# 05_MCU_C.net
KiCad netlist of a schematic drawn in Altium Designer
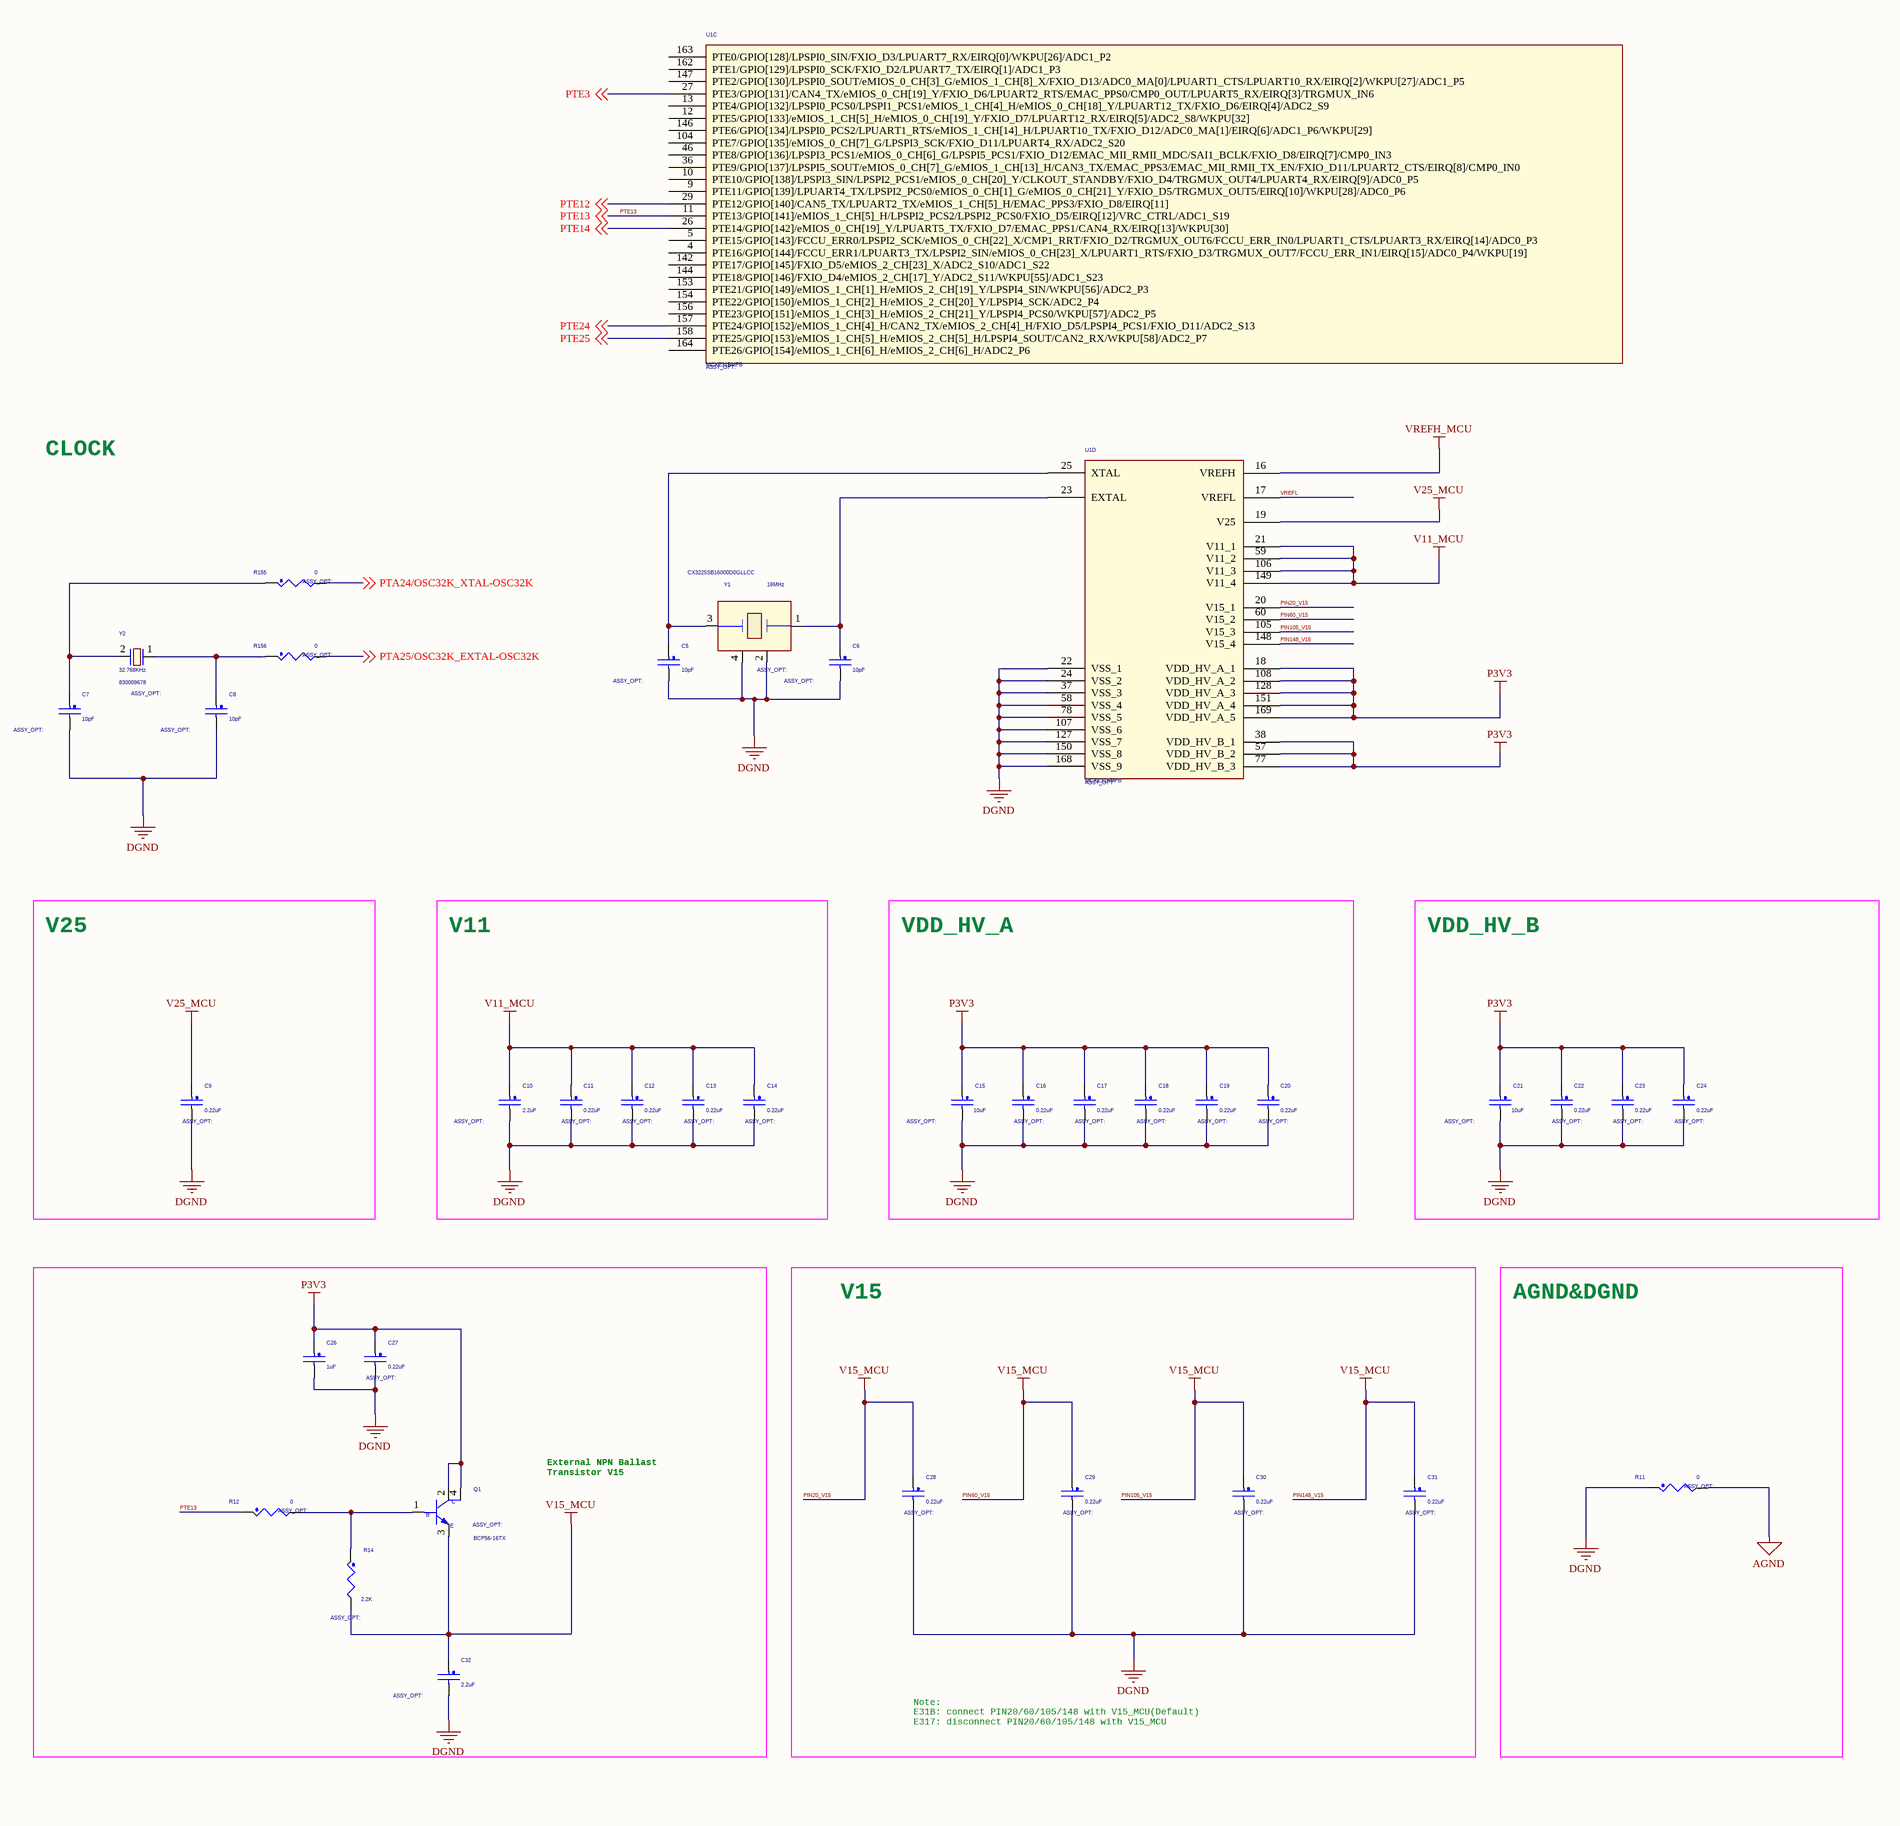
[diagram p0: 05 MCU_C.SchDoc, left]
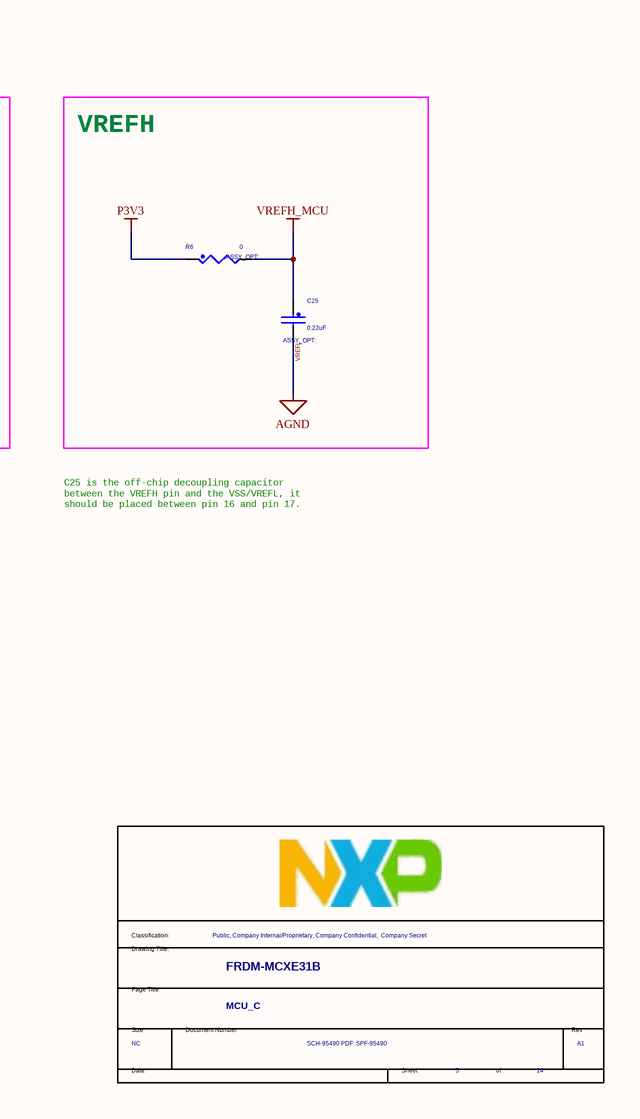
[diagram p1: 05 MCU_C.SchDoc, right]

(export (version "E")
  (design (tool "Eeschema 10.0.6"))
  (components
    (comp (ref "C5")
      (value "10pF")
      (footprint "CC0402_25")
      (description "CAP CER 10pF 50V 5% C0G AEC-Q200 0402")
      (fields (field (name "TOLERANCE") "5%") (field (name "VOLTAGE") "50V"))
      (libsource (lib "*") (part "CAP_NP"))
    )
    (comp (ref "C6")
      (value "10pF")
      (footprint "CC0402_25")
      (description "CAP CER 10pF 50V 5% C0G AEC-Q200 0402")
      (fields (field (name "VOLTAGE") "50V") (field (name "TOLERANCE") "5%"))
      (libsource (lib "*") (part "CAP_NP"))
    )
    (comp (ref "C7")
      (value "10pF")
      (footprint "CC0402_25")
      (description "CAP CER 10pF 50V 5% C0G AEC-Q200 0402")
      (fields (field (name "VOLTAGE") "50V") (field (name "TOLERANCE") "5%"))
      (libsource (lib "*") (part "CAP_NP"))
    )
    (comp (ref "C8")
      (value "10pF")
      (footprint "CC0402_25")
      (description "CAP CER 10pF 50V 5% C0G AEC-Q200 0402")
      (fields (field (name "VOLTAGE") "50V") (field (name "TOLERANCE") "5%"))
      (libsource (lib "*") (part "CAP_NP"))
    )
    (comp (ref "C9")
      (value "0.22uF")
      (footprint "CC0402_25")
      (description "CAP CER 0.22UF 16V 10% X7R 0402")
      (fields (field (name "TOLERANCE") "10%") (field (name "VOLTAGE") "16V"))
      (libsource (lib "*") (part "CAP_NP"))
    )
    (comp (ref "C10")
      (value "2.2uF")
      (footprint "CC0402_25")
      (description "CAP CER 2.2UF 10V 20% X5R 0402")
      (fields (field (name "TOLERANCE") "20%"))
      (libsource (lib "*") (part "CAP_NP"))
    )
    (comp (ref "C11")
      (value "0.22uF")
      (footprint "CC0402_25")
      (description "CAP CER 0.22UF 16V 10% X7R 0402")
      (fields (field (name "TOLERANCE") "10%") (field (name "VOLTAGE") "16V"))
      (libsource (lib "*") (part "CAP_NP"))
    )
    (comp (ref "C12")
      (value "0.22uF")
      (footprint "CC0402_25")
      (description "CAP CER 0.22UF 16V 10% X7R 0402")
      (fields (field (name "TOLERANCE") "10%") (field (name "VOLTAGE") "16V"))
      (libsource (lib "*") (part "CAP_NP"))
    )
    (comp (ref "C13")
      (value "0.22uF")
      (footprint "CC0402_25")
      (description "CAP CER 0.22UF 16V 10% X7R 0402")
      (fields (field (name "TOLERANCE") "10%") (field (name "VOLTAGE") "16V"))
      (libsource (lib "*") (part "CAP_NP"))
    )
    (comp (ref "C14")
      (value "0.22uF")
      (footprint "CC0402_25")
      (description "CAP CER 0.22UF 16V 10% X7R 0402")
      (fields (field (name "TOLERANCE") "10%") (field (name "VOLTAGE") "16V"))
      (libsource (lib "*") (part "CAP_NP"))
    )
    (comp (ref "C15")
      (value "10uF")
      (footprint "CC0603_OV")
      (description "CAP CER 10uF 25V 20% X5R 0603")
      (fields (field (name "TOLERANCE") "20%"))
      (libsource (lib "*") (part "CAP_NP"))
    )
    (comp (ref "C16")
      (value "0.22uF")
      (footprint "CC0402_25")
      (description "CAP CER 0.22UF 16V 10% X7R 0402")
      (fields (field (name "TOLERANCE") "10%") (field (name "VOLTAGE") "16V"))
      (libsource (lib "*") (part "CAP_NP"))
    )
    (comp (ref "C17")
      (value "0.22uF")
      (footprint "CC0402_25")
      (description "CAP CER 0.22UF 16V 10% X7R 0402")
      (fields (field (name "TOLERANCE") "10%") (field (name "VOLTAGE") "16V"))
      (libsource (lib "*") (part "CAP_NP"))
    )
    (comp (ref "C18")
      (value "0.22uF")
      (footprint "CC0402_25")
      (description "CAP CER 0.22UF 16V 10% X7R 0402")
      (fields (field (name "TOLERANCE") "10%") (field (name "VOLTAGE") "16V"))
      (libsource (lib "*") (part "CAP_NP"))
    )
    (comp (ref "C19")
      (value "0.22uF")
      (footprint "CC0402_25")
      (description "CAP CER 0.22UF 16V 10% X7R 0402")
      (fields (field (name "TOLERANCE") "10%") (field (name "VOLTAGE") "16V"))
      (libsource (lib "*") (part "CAP_NP"))
    )
    (comp (ref "C20")
      (value "0.22uF")
      (footprint "CC0402_25")
      (description "CAP CER 0.22UF 16V 10% X7R 0402")
      (fields (field (name "TOLERANCE") "10%") (field (name "VOLTAGE") "16V"))
      (libsource (lib "*") (part "CAP_NP"))
    )
    (comp (ref "C21")
      (value "10uF")
      (footprint "CC0603_OV")
      (description "CAP CER 10uF 25V 20% X5R 0603")
      (fields (field (name "TOLERANCE") "20%"))
      (libsource (lib "*") (part "CAP_NP"))
    )
    (comp (ref "C22")
      (value "0.22uF")
      (footprint "CC0402_25")
      (description "CAP CER 0.22UF 16V 10% X7R 0402")
      (fields (field (name "VOLTAGE") "16V") (field (name "TOLERANCE") "10%"))
      (libsource (lib "*") (part "CAP_NP"))
    )
    (comp (ref "C23")
      (value "0.22uF")
      (footprint "CC0402_25")
      (description "CAP CER 0.22UF 16V 10% X7R 0402")
      (fields (field (name "VOLTAGE") "16V") (field (name "TOLERANCE") "10%"))
      (libsource (lib "*") (part "CAP_NP"))
    )
    (comp (ref "C24")
      (value "0.22uF")
      (footprint "CC0402_25")
      (description "CAP CER 0.22UF 16V 10% X7R 0402")
      (fields (field (name "VOLTAGE") "16V") (field (name "TOLERANCE") "10%"))
      (libsource (lib "*") (part "CAP_NP"))
    )
    (comp (ref "C25")
      (value "0.22uF")
      (footprint "CC0402_25")
      (description "CAP CER 0.22UF 16V 10% X7R 0402")
      (fields (field (name "TOLERANCE") "10%") (field (name "VOLTAGE") "16V"))
      (libsource (lib "*") (part "CAP_NP"))
    )
    (comp (ref "C26")
      (value "1uF")
      (footprint "CC0402_25")
      (description "CAP CER 1.0uF 16V 10% X6S 0402")
      (fields (field (name "VOLTAGE") "16V") (field (name "TOLERANCE") "10%"))
      (libsource (lib "*") (part "CAP_NP"))
    )
    (comp (ref "C27")
      (value "0.22uF")
      (footprint "CC0402_25")
      (description "CAP CER 0.22UF 16V 10% X7R 0402")
      (fields (field (name "TOLERANCE") "10%") (field (name "VOLTAGE") "16V"))
      (libsource (lib "*") (part "CAP_NP"))
    )
    (comp (ref "C28")
      (value "0.22uF")
      (footprint "CC0402_25")
      (description "CAP CER 0.22UF 16V 10% X7R 0402")
      (fields (field (name "VOLTAGE") "16V") (field (name "TOLERANCE") "10%"))
      (libsource (lib "*") (part "CAP_NP"))
    )
    (comp (ref "C29")
      (value "0.22uF")
      (footprint "CC0402_25")
      (description "CAP CER 0.22UF 16V 10% X7R 0402")
      (fields (field (name "VOLTAGE") "16V") (field (name "TOLERANCE") "10%"))
      (libsource (lib "*") (part "CAP_NP"))
    )
    (comp (ref "C30")
      (value "0.22uF")
      (footprint "CC0402_25")
      (description "CAP CER 0.22UF 16V 10% X7R 0402")
      (fields (field (name "VOLTAGE") "16V") (field (name "TOLERANCE") "10%"))
      (libsource (lib "*") (part "CAP_NP"))
    )
    (comp (ref "C31")
      (value "0.22uF")
      (footprint "CC0402_25")
      (description "CAP CER 0.22UF 16V 10% X7R 0402")
      (fields (field (name "VOLTAGE") "16V") (field (name "TOLERANCE") "10%"))
      (libsource (lib "*") (part "CAP_NP"))
    )
    (comp (ref "C32")
      (value "2.2uF")
      (footprint "CC0402_25")
      (description "CAP CER 2.2UF 10V 20% X5R 0402")
      (fields (field (name "TOLERANCE") "20%"))
      (libsource (lib "*") (part "CAP_NP"))
    )
    (comp (ref "Q1")
      (value "BCP56-16TX")
      (footprint "SOT223")
      (description "TRANS NPN 80V 1A AEC-Q101 SOT223")
      (fields (field (name "MFG_PN01") "BCP56-16TX"))
      (libsource (lib "*") (part "TRAN_NPN_SOT223"))
    )
    (comp (ref "R6")
      (value "0")
      (footprint "RC0402_25")
      (description "RES MF ZERO OHM 1/10W -- 0603")
      (fields (field (name "VOLTAGE") "1/16W"))
      (libsource (lib "*") (part "RES"))
    )
    (comp (ref "R11")
      (value "0")
      (footprint "RC0603_OV")
      (description "RES MF ZERO OHM 1/10W -- 0603")
      (fields (field (name "VOLTAGE") "1/16W"))
      (libsource (lib "*") (part "RES"))
    )
    (comp (ref "R12")
      (value "0")
      (footprint "RC0603_OV")
      (description "RES MF ZERO OHM 1/10W -- 0603")
      (fields (field (name "VOLTAGE") "1/16W"))
      (libsource (lib "*") (part "RES"))
    )
    (comp (ref "R14")
      (value "2.2K")
      (footprint "RC0402_25")
      (description "RES MF 2.2K 1/16W 1% 0402")
      (libsource (lib "*") (part "RES"))
    )
    (comp (ref "R155")
      (value "0")
      (footprint "RC0402_25")
      (description "RES MF ZERO OHM 1/10W -- 0603")
      (fields (field (name "VOLTAGE") "1/16W"))
      (libsource (lib "*") (part "RES"))
    )
    (comp (ref "R156")
      (value "0")
      (footprint "RC0402_25")
      (description "RES MF ZERO OHM 1/10W -- 0603")
      (fields (field (name "VOLTAGE") "1/16W"))
      (libsource (lib "*") (part "RES"))
    )
    (comp (ref "U1")
      (value "MCXE31BMPB")
      (footprint "QFP-172_L16.0-W16.0-P0.65-LS19.0-TL")
      (description "IC MCU 4M FLASH 2.97-5.5V 160MHZ HDQFP172")
      (fields (field (name "MFG_PN01") "MCXE31BMPB"))
      (libsource (lib "*") (part "MCXE318MPB_172P"))
    )
    (comp (ref "Y1")
      (value "16MHz")
      (footprint "X322516MLB4SI")
      (description "XTAL 16MHz 8pF 15PPM 3225 SMT")
      (fields (field (name "MFG_PN01") "CX3225SB16000D0GLLCC"))
      (libsource (lib "*") (part "XTAL_13"))
    )
    (comp (ref "Y2")
      (value "32.768KHz")
      (footprint "XTAL2-3p2x1p5-SM")
      (description "XTAL 32.768kHz 12.5pF 1.05pF 20ppm SMT")
      (fields (field (name "MFG_PN01") "830009678"))
      (libsource (lib "*") (part "CRYSTAL"))
    )
  )
  (nets
    (net (code "1") (name "AGND") (class "Default")
      (node (ref "C25") (pin "2") (pinfunction "2_2") (pintype "passive"))
      (node (ref "R11") (pin "2") (pinfunction "2_2") (pintype "passive"))
      (node (ref "U1") (pin "17") (pinfunction "VREFL_17") (pintype "passive"))
    )
    (net (code "2") (name "DGND") (class "Default")
      (node (ref "C10") (pin "2") (pinfunction "2_2") (pintype "passive"))
      (node (ref "C11") (pin "2") (pinfunction "2_2") (pintype "passive"))
      (node (ref "C12") (pin "2") (pinfunction "2_2") (pintype "passive"))
      (node (ref "C13") (pin "2") (pinfunction "2_2") (pintype "passive"))
      (node (ref "C14") (pin "2") (pinfunction "2_2") (pintype "passive"))
      (node (ref "C15") (pin "2") (pinfunction "2_2") (pintype "passive"))
      (node (ref "C16") (pin "2") (pinfunction "2_2") (pintype "passive"))
      (node (ref "C17") (pin "2") (pinfunction "2_2") (pintype "passive"))
      (node (ref "C18") (pin "2") (pinfunction "2_2") (pintype "passive"))
      (node (ref "C19") (pin "2") (pinfunction "2_2") (pintype "passive"))
      (node (ref "C20") (pin "2") (pinfunction "2_2") (pintype "passive"))
      (node (ref "C21") (pin "2") (pinfunction "2_2") (pintype "passive"))
      (node (ref "C22") (pin "2") (pinfunction "2_2") (pintype "passive"))
      (node (ref "C23") (pin "2") (pinfunction "2_2") (pintype "passive"))
      (node (ref "C24") (pin "2") (pinfunction "2_2") (pintype "passive"))
      (node (ref "C26") (pin "2") (pinfunction "2_2") (pintype "passive"))
      (node (ref "C27") (pin "2") (pinfunction "2_2") (pintype "passive"))
      (node (ref "C28") (pin "2") (pinfunction "2_2") (pintype "passive"))
      (node (ref "C29") (pin "2") (pinfunction "2_2") (pintype "passive"))
      (node (ref "C30") (pin "2") (pinfunction "2_2") (pintype "passive"))
      (node (ref "C31") (pin "2") (pinfunction "2_2") (pintype "passive"))
      (node (ref "C32") (pin "2") (pinfunction "2_2") (pintype "passive"))
      (node (ref "C5") (pin "2") (pinfunction "2_2") (pintype "passive"))
      (node (ref "C6") (pin "2") (pinfunction "2_2") (pintype "passive"))
      (node (ref "C7") (pin "2") (pinfunction "2_2") (pintype "passive"))
      (node (ref "C8") (pin "2") (pinfunction "2_2") (pintype "passive"))
      (node (ref "C9") (pin "2") (pinfunction "2_2") (pintype "passive"))
      (node (ref "R11") (pin "1") (pinfunction "1_1") (pintype "passive"))
      (node (ref "U1") (pin "107") (pinfunction "VSS_6_107") (pintype "power_in"))
      (node (ref "U1") (pin "127") (pinfunction "VSS_7_127") (pintype "power_in"))
      (node (ref "U1") (pin "150") (pinfunction "VSS_8_150") (pintype "power_in"))
      (node (ref "U1") (pin "168") (pinfunction "VSS_9_168") (pintype "power_in"))
      (node (ref "U1") (pin "22") (pinfunction "VSS_1_22") (pintype "power_in"))
      (node (ref "U1") (pin "24") (pinfunction "VSS_2_24") (pintype "power_in"))
      (node (ref "U1") (pin "37") (pinfunction "VSS_3_37") (pintype "power_in"))
      (node (ref "U1") (pin "58") (pinfunction "VSS_4_58") (pintype "power_in"))
      (node (ref "U1") (pin "78") (pinfunction "VSS_5_78") (pintype "power_in"))
      (node (ref "Y1") (pin "2") (pinfunction "2_2") (pintype "passive"))
      (node (ref "Y1") (pin "4") (pinfunction "4_4") (pintype "passive"))
    )
    (net (code "3") (name "Net-(C7-Pad1)") (class "Default")
      (node (ref "C7") (pin "1") (pinfunction "1_1") (pintype "passive"))
      (node (ref "R155") (pin "1") (pinfunction "1_1") (pintype "passive"))
      (node (ref "Y2") (pin "2") (pinfunction "2_2") (pintype "passive"))
    )
    (net (code "4") (name "Net-(C8-Pad1)") (class "Default")
      (node (ref "C8") (pin "1") (pinfunction "1_1") (pintype "passive"))
      (node (ref "R156") (pin "1") (pinfunction "1_1") (pintype "passive"))
      (node (ref "Y2") (pin "1") (pinfunction "1_1") (pintype "passive"))
    )
    (net (code "5") (name "Net-(Q1-BASE)") (class "Default")
      (node (ref "Q1") (pin "1") (pinfunction "BASE_1") (pintype "passive"))
      (node (ref "R12") (pin "2") (pinfunction "2_2") (pintype "passive"))
      (node (ref "R14") (pin "1") (pinfunction "1_1") (pintype "passive"))
    )
    (net (code "6") (name "Net-(U1D-EXTAL)") (class "Default")
      (node (ref "C6") (pin "1") (pinfunction "1_1") (pintype "passive"))
      (node (ref "U1") (pin "23") (pinfunction "EXTAL_23") (pintype "passive"))
      (node (ref "Y1") (pin "1") (pinfunction "1_1") (pintype "passive"))
    )
    (net (code "7") (name "Net-(U1D-XTAL)") (class "Default")
      (node (ref "C5") (pin "1") (pinfunction "1_1") (pintype "passive"))
      (node (ref "U1") (pin "25") (pinfunction "XTAL_25") (pintype "passive"))
      (node (ref "Y1") (pin "3") (pinfunction "3_3") (pintype "passive"))
    )
    (net (code "8") (name "P3V3") (class "Default")
      (node (ref "C15") (pin "1") (pinfunction "1_1") (pintype "passive"))
      (node (ref "C16") (pin "1") (pinfunction "1_1") (pintype "passive"))
      (node (ref "C17") (pin "1") (pinfunction "1_1") (pintype "passive"))
      (node (ref "C18") (pin "1") (pinfunction "1_1") (pintype "passive"))
      (node (ref "C19") (pin "1") (pinfunction "1_1") (pintype "passive"))
      (node (ref "C20") (pin "1") (pinfunction "1_1") (pintype "passive"))
      (node (ref "C21") (pin "1") (pinfunction "1_1") (pintype "passive"))
      (node (ref "C22") (pin "1") (pinfunction "1_1") (pintype "passive"))
      (node (ref "C23") (pin "1") (pinfunction "1_1") (pintype "passive"))
      (node (ref "C24") (pin "1") (pinfunction "1_1") (pintype "passive"))
      (node (ref "C26") (pin "1") (pinfunction "1_1") (pintype "passive"))
      (node (ref "C27") (pin "1") (pinfunction "1_1") (pintype "passive"))
      (node (ref "Q1") (pin "2") (pinfunction "COLLECTOR_2") (pintype "passive"))
      (node (ref "Q1") (pin "4") (pinfunction "COLLECTOR1_4") (pintype "passive"))
      (node (ref "R6") (pin "1") (pinfunction "1_1") (pintype "passive"))
      (node (ref "U1") (pin "108") (pinfunction "VDD_HV_A_2_108") (pintype "power_in"))
      (node (ref "U1") (pin "128") (pinfunction "VDD_HV_A_3_128") (pintype "power_in"))
      (node (ref "U1") (pin "151") (pinfunction "VDD_HV_A_4_151") (pintype "power_in"))
      (node (ref "U1") (pin "169") (pinfunction "VDD_HV_A_5_169") (pintype "power_in"))
      (node (ref "U1") (pin "18") (pinfunction "VDD_HV_A_1_18") (pintype "power_in"))
      (node (ref "U1") (pin "38") (pinfunction "VDD_HV_B_1_38") (pintype "power_in"))
      (node (ref "U1") (pin "57") (pinfunction "VDD_HV_B_2_57") (pintype "power_in"))
      (node (ref "U1") (pin "77") (pinfunction "VDD_HV_B_3_77") (pintype "power_in"))
    )
    (net (code "9") (name "PTA24{slash}OSC32K_XTAL-OSC32K") (class "Default")
      (node (ref "R155") (pin "2") (pinfunction "2_2") (pintype "passive"))
    )
    (net (code "10") (name "PTA25{slash}OSC32K_EXTAL-OSC32K") (class "Default")
      (node (ref "R156") (pin "2") (pinfunction "2_2") (pintype "passive"))
    )
    (net (code "11") (name "PTE3") (class "Default")
      (node (ref "U1") (pin "27") (pinfunction "PTE3/GPIO[131]/CAN4_TX/eMIOS_0_CH[19]_Y/FXIO_D6/LPUART2_RTS/EMAC_PPS0/CMP0_OUT/LPUART5_RX/EIRQ[3]/TRGMUX_IN6_27") (pintype "passive"))
    )
    (net (code "12") (name "PTE12") (class "Default")
      (node (ref "U1") (pin "29") (pinfunction "PTE12/GPIO[140]/CAN5_TX/LPUART2_TX/eMIOS_1_CH[5]_H/EMAC_PPS3/FXIO_D8/EIRQ[11]_29") (pintype "passive"))
    )
    (net (code "13") (name "PTE13") (class "Default")
      (node (ref "R12") (pin "1") (pinfunction "1_1") (pintype "passive"))
      (node (ref "U1") (pin "11") (pinfunction "PTE13/GPIO[141]/eMIOS_1_CH[5]_H/LPSPI2_PCS2/LPSPI2_PCS0/FXIO_D5/EIRQ[12]/VRC_CTRL/ADC1_S19_11") (pintype "passive"))
    )
    (net (code "14") (name "PTE14") (class "Default")
      (node (ref "U1") (pin "26") (pinfunction "PTE14/GPIO[142]/eMIOS_0_CH[19]_Y/LPUART5_TX/FXIO_D7/EMAC_PPS1/CAN4_RX/EIRQ[13]/WKPU[30]_26") (pintype "passive"))
    )
    (net (code "15") (name "PTE24") (class "Default")
      (node (ref "U1") (pin "157") (pinfunction "PTE24/GPIO[152]/eMIOS_1_CH[4]_H/CAN2_TX/eMIOS_2_CH[4]_H/FXIO_D5/LPSPI4_PCS1/FXIO_D11/ADC2_S13_157") (pintype "passive"))
    )
    (net (code "16") (name "PTE25") (class "Default")
      (node (ref "U1") (pin "158") (pinfunction "PTE25/GPIO[153]/eMIOS_1_CH[5]_H/eMIOS_2_CH[5]_H/LPSPI4_SOUT/CAN2_RX/WKPU[58]/ADC2_P7_158") (pintype "passive"))
    )
    (net (code "17") (name "V11_MCU") (class "Default")
      (node (ref "C10") (pin "1") (pinfunction "1_1") (pintype "passive"))
      (node (ref "C11") (pin "1") (pinfunction "1_1") (pintype "passive"))
      (node (ref "C12") (pin "1") (pinfunction "1_1") (pintype "passive"))
      (node (ref "C13") (pin "1") (pinfunction "1_1") (pintype "passive"))
      (node (ref "C14") (pin "1") (pinfunction "1_1") (pintype "passive"))
      (node (ref "U1") (pin "106") (pinfunction "V11_3_106") (pintype "passive"))
      (node (ref "U1") (pin "149") (pinfunction "V11_4_149") (pintype "passive"))
      (node (ref "U1") (pin "21") (pinfunction "V11_1_21") (pintype "passive"))
      (node (ref "U1") (pin "59") (pinfunction "V11_2_59") (pintype "passive"))
    )
    (net (code "18") (name "V15_MCU") (class "Default")
      (node (ref "C28") (pin "1") (pinfunction "1_1") (pintype "passive"))
      (node (ref "C29") (pin "1") (pinfunction "1_1") (pintype "passive"))
      (node (ref "C30") (pin "1") (pinfunction "1_1") (pintype "passive"))
      (node (ref "C31") (pin "1") (pinfunction "1_1") (pintype "passive"))
      (node (ref "C32") (pin "1") (pinfunction "1_1") (pintype "passive"))
      (node (ref "Q1") (pin "3") (pinfunction "EMITTER_3") (pintype "passive"))
      (node (ref "R14") (pin "2") (pinfunction "2_2") (pintype "passive"))
      (node (ref "U1") (pin "105") (pinfunction "V15_3_105") (pintype "passive"))
      (node (ref "U1") (pin "148") (pinfunction "V15_4_148") (pintype "passive"))
      (node (ref "U1") (pin "20") (pinfunction "V15_1_20") (pintype "passive"))
      (node (ref "U1") (pin "60") (pinfunction "V15_2_60") (pintype "passive"))
    )
    (net (code "19") (name "V25_MCU") (class "Default")
      (node (ref "C9") (pin "1") (pinfunction "1_1") (pintype "passive"))
      (node (ref "U1") (pin "19") (pinfunction "V25_19") (pintype "passive"))
    )
    (net (code "20") (name "VREFH_MCU") (class "Default")
      (node (ref "C25") (pin "1") (pinfunction "1_1") (pintype "passive"))
      (node (ref "R6") (pin "2") (pinfunction "2_2") (pintype "passive"))
      (node (ref "U1") (pin "16") (pinfunction "VREFH_16") (pintype "passive"))
    )
    (net (code "21") (name "unconnected-(U1C-PTE0{slash}GPIO[128]{slash}LPSPI0_SIN{slash}FXIO_D3{slash}LPUART7_RX{slash}EIRQ[0]{slash}WKPU[26]{slash}ADC1_P2-Pad163)") (class "Default")
      (node (ref "U1") (pin "163") (pinfunction "PTE0/GPIO[128]/LPSPI0_SIN/FXIO_D3/LPUART7_RX/EIRQ[0]/WKPU[26]/ADC1_P2_163") (pintype "passive"))
    )
    (net (code "22") (name "unconnected-(U1C-PTE1{slash}GPIO[129]{slash}LPSPI0_SCK{slash}FXIO_D2{slash}LPUART7_TX{slash}EIRQ[1]{slash}ADC1_P3-Pad162)") (class "Default")
      (node (ref "U1") (pin "162") (pinfunction "PTE1/GPIO[129]/LPSPI0_SCK/FXIO_D2/LPUART7_TX/EIRQ[1]/ADC1_P3_162") (pintype "passive"))
    )
    (net (code "23") (name "unconnected-(U1C-PTE2{slash}GPIO[130]{slash}LPSPI0_SOUT{slash}eMIOS_0_CH[3]_G{slash}eMIOS_1_CH[8]_X{slash}FXIO_D13{slash}ADC0_MA[0]{slash}LPUART1_CTS{slash}LPUART10_RX{slash}EIRQ[2]{slash}WKPU[27]{slash}ADC1_P5-Pad147)") (class "Default")
      (node (ref "U1") (pin "147") (pinfunction "PTE2/GPIO[130]/LPSPI0_SOUT/eMIOS_0_CH[3]_G/eMIOS_1_CH[8]_X/FXIO_D13/ADC0_MA[0]/LPUART1_CTS/LPUART10_RX/EIRQ[2]/WKPU[27]/ADC1_P5_147") (pintype "passive"))
    )
    (net (code "24") (name "unconnected-(U1C-PTE4{slash}GPIO[132]{slash}LPSPI0_PCS0{slash}LPSPI1_PCS1{slash}eMIOS_1_CH[4]_H{slash}eMIOS_0_CH[18]_Y{slash}LPUART12_TX{slash}FXIO_D6{slash}EIRQ[4]{slash}ADC2_S9-Pad13)") (class "Default")
      (node (ref "U1") (pin "13") (pinfunction "PTE4/GPIO[132]/LPSPI0_PCS0/LPSPI1_PCS1/eMIOS_1_CH[4]_H/eMIOS_0_CH[18]_Y/LPUART12_TX/FXIO_D6/EIRQ[4]/ADC2_S9_13") (pintype "passive"))
    )
    (net (code "25") (name "unconnected-(U1C-PTE5{slash}GPIO[133]{slash}eMIOS_1_CH[5]_H{slash}eMIOS_0_CH[19]_Y{slash}FXIO_D7{slash}LPUART12_RX{slash}EIRQ[5]{slash}ADC2_S8{slash}WKPU[32]-Pad12)") (class "Default")
      (node (ref "U1") (pin "12") (pinfunction "PTE5/GPIO[133]/eMIOS_1_CH[5]_H/eMIOS_0_CH[19]_Y/FXIO_D7/LPUART12_RX/EIRQ[5]/ADC2_S8/WKPU[32]_12") (pintype "passive"))
    )
    (net (code "26") (name "unconnected-(U1C-PTE6{slash}GPIO[134]{slash}LPSPI0_PCS2{slash}LPUART1_RTS{slash}eMIOS_1_CH[14]_H{slash}LPUART10_TX{slash}FXIO_D12{slash}ADC0_MA[1]{slash}EIRQ[6]{slash}ADC1_P6{slash}WKPU[29]-Pad146)") (class "Default")
      (node (ref "U1") (pin "146") (pinfunction "PTE6/GPIO[134]/LPSPI0_PCS2/LPUART1_RTS/eMIOS_1_CH[14]_H/LPUART10_TX/FXIO_D12/ADC0_MA[1]/EIRQ[6]/ADC1_P6/WKPU[29]_146") (pintype "passive"))
    )
    (net (code "27") (name "unconnected-(U1C-PTE7{slash}GPIO[135]{slash}eMIOS_0_CH[7]_G{slash}LPSPI3_SCK{slash}FXIO_D11{slash}LPUART4_RX{slash}ADC2_S20-Pad104)") (class "Default")
      (node (ref "U1") (pin "104") (pinfunction "PTE7/GPIO[135]/eMIOS_0_CH[7]_G/LPSPI3_SCK/FXIO_D11/LPUART4_RX/ADC2_S20_104") (pintype "passive"))
    )
    (net (code "28") (name "unconnected-(U1C-PTE8{slash}GPIO[136]{slash}LPSPI3_PCS1{slash}eMIOS_0_CH[6]_G{slash}LPSPI5_PCS1{slash}FXIO_D12{slash}EMAC_MII_RMII_MDC{slash}SAI1_BCLK{slash}FXIO_D8{slash}EIRQ[7]{slash}CMP0_IN3-Pad46)") (class "Default")
      (node (ref "U1") (pin "46") (pinfunction "PTE8/GPIO[136]/LPSPI3_PCS1/eMIOS_0_CH[6]_G/LPSPI5_PCS1/FXIO_D12/EMAC_MII_RMII_MDC/SAI1_BCLK/FXIO_D8/EIRQ[7]/CMP0_IN3_46") (pintype "passive"))
    )
    (net (code "29") (name "unconnected-(U1C-PTE9{slash}GPIO[137]{slash}LPSPI5_SOUT{slash}eMIOS_0_CH[7]_G{slash}eMIOS_1_CH[13]_H{slash}CAN3_TX{slash}EMAC_PPS3{slash}EMAC_MII_RMII_TX_EN{slash}FXIO_D11{slash}LPUART2_CTS{slash}EIRQ[8]{slash}CMP0_IN0-Pad36)") (class "Default")
      (node (ref "U1") (pin "36") (pinfunction "PTE9/GPIO[137]/LPSPI5_SOUT/eMIOS_0_CH[7]_G/eMIOS_1_CH[13]_H/CAN3_TX/EMAC_PPS3/EMAC_MII_RMII_TX_EN/FXIO_D11/LPUART2_CTS/EIRQ[8]/CMP0_IN0_36") (pintype "passive"))
    )
    (net (code "30") (name "unconnected-(U1C-PTE10{slash}GPIO[138]{slash}LPSPI3_SIN{slash}LPSPI2_PCS1{slash}eMIOS_0_CH[20]_Y{slash}CLKOUT_STANDBY{slash}FXIO_D4{slash}TRGMUX_OUT4{slash}LPUART4_RX{slash}EIRQ[9]{slash}ADC0_P5-Pad10)") (class "Default")
      (node (ref "U1") (pin "10") (pinfunction "PTE10/GPIO[138]/LPSPI3_SIN/LPSPI2_PCS1/eMIOS_0_CH[20]_Y/CLKOUT_STANDBY/FXIO_D4/TRGMUX_OUT4/LPUART4_RX/EIRQ[9]/ADC0_P5_10") (pintype "passive"))
    )
    (net (code "31") (name "unconnected-(U1C-PTE11{slash}GPIO[139]{slash}LPUART4_TX{slash}LPSPI2_PCS0{slash}eMIOS_0_CH[1]_G{slash}eMIOS_0_CH[21]_Y{slash}FXIO_D5{slash}TRGMUX_OUT5{slash}EIRQ[10]{slash}WKPU[28]{slash}ADC0_P6-Pad9)") (class "Default")
      (node (ref "U1") (pin "9") (pinfunction "PTE11/GPIO[139]/LPUART4_TX/LPSPI2_PCS0/eMIOS_0_CH[1]_G/eMIOS_0_CH[21]_Y/FXIO_D5/TRGMUX_OUT5/EIRQ[10]/WKPU[28]/ADC0_P6_9") (pintype "passive"))
    )
    (net (code "32") (name "unconnected-(U1C-PTE15{slash}GPIO[143]{slash}FCCU_ERR0{slash}LPSPI2_SCK{slash}eMIOS_0_CH[22]_X{slash}CMP1_RRT{slash}FXIO_D2{slash}TRGMUX_OUT6{slash}FCCU_ERR_IN0{slash}LPUART1_CTS{slash}LPUART3_RX{slash}EIRQ[14]{slash}ADC0_P3-Pad5)") (class "Default")
      (node (ref "U1") (pin "5") (pinfunction "PTE15/GPIO[143]/FCCU_ERR0/LPSPI2_SCK/eMIOS_0_CH[22]_X/CMP1_RRT/FXIO_D2/TRGMUX_OUT6/FCCU_ERR_IN0/LPUART1_CTS/LPUART3_RX/EIRQ[14]/ADC0_P3_5") (pintype "passive"))
    )
    (net (code "33") (name "unconnected-(U1C-PTE16{slash}GPIO[144]{slash}FCCU_ERR1{slash}LPUART3_TX{slash}LPSPI2_SIN{slash}eMIOS_0_CH[23]_X{slash}LPUART1_RTS{slash}FXIO_D3{slash}TRGMUX_OUT7{slash}FCCU_ERR_IN1{slash}EIRQ[15]{slash}ADC0_P4{slash}WKPU[19]-Pad4)") (class "Default")
      (node (ref "U1") (pin "4") (pinfunction "PTE16/GPIO[144]/FCCU_ERR1/LPUART3_TX/LPSPI2_SIN/eMIOS_0_CH[23]_X/LPUART1_RTS/FXIO_D3/TRGMUX_OUT7/FCCU_ERR_IN1/EIRQ[15]/ADC0_P4/WKPU[19]_4") (pintype "passive"))
    )
    (net (code "34") (name "unconnected-(U1C-PTE17{slash}GPIO[145]{slash}FXIO_D5{slash}eMIOS_2_CH[23]_X{slash}ADC2_S10{slash}ADC1_S22-Pad142)") (class "Default")
      (node (ref "U1") (pin "142") (pinfunction "PTE17/GPIO[145]/FXIO_D5/eMIOS_2_CH[23]_X/ADC2_S10/ADC1_S22_142") (pintype "passive"))
    )
    (net (code "35") (name "unconnected-(U1C-PTE18{slash}GPIO[146]{slash}FXIO_D4{slash}eMIOS_2_CH[17]_Y{slash}ADC2_S11{slash}WKPU[55]{slash}ADC1_S23-Pad144)") (class "Default")
      (node (ref "U1") (pin "144") (pinfunction "PTE18/GPIO[146]/FXIO_D4/eMIOS_2_CH[17]_Y/ADC2_S11/WKPU[55]/ADC1_S23_144") (pintype "passive"))
    )
    (net (code "36") (name "unconnected-(U1C-PTE21{slash}GPIO[149]{slash}eMIOS_1_CH[1]_H{slash}eMIOS_2_CH[19]_Y{slash}LPSPI4_SIN{slash}WKPU[56]{slash}ADC2_P3-Pad153)") (class "Default")
      (node (ref "U1") (pin "153") (pinfunction "PTE21/GPIO[149]/eMIOS_1_CH[1]_H/eMIOS_2_CH[19]_Y/LPSPI4_SIN/WKPU[56]/ADC2_P3_153") (pintype "passive"))
    )
    (net (code "37") (name "unconnected-(U1C-PTE22{slash}GPIO[150]{slash}eMIOS_1_CH[2]_H{slash}eMIOS_2_CH[20]_Y{slash}LPSPI4_SCK{slash}ADC2_P4-Pad154)") (class "Default")
      (node (ref "U1") (pin "154") (pinfunction "PTE22/GPIO[150]/eMIOS_1_CH[2]_H/eMIOS_2_CH[20]_Y/LPSPI4_SCK/ADC2_P4_154") (pintype "passive"))
    )
    (net (code "38") (name "unconnected-(U1C-PTE23{slash}GPIO[151]{slash}eMIOS_1_CH[3]_H{slash}eMIOS_2_CH[21]_Y{slash}LPSPI4_PCS0{slash}WKPU[57]{slash}ADC2_P5-Pad156)") (class "Default")
      (node (ref "U1") (pin "156") (pinfunction "PTE23/GPIO[151]/eMIOS_1_CH[3]_H/eMIOS_2_CH[21]_Y/LPSPI4_PCS0/WKPU[57]/ADC2_P5_156") (pintype "passive"))
    )
    (net (code "39") (name "unconnected-(U1C-PTE26{slash}GPIO[154]{slash}eMIOS_1_CH[6]_H{slash}eMIOS_2_CH[6]_H{slash}ADC2_P6-Pad164)") (class "Default")
      (node (ref "U1") (pin "164") (pinfunction "PTE26/GPIO[154]/eMIOS_1_CH[6]_H/eMIOS_2_CH[6]_H/ADC2_P6_164") (pintype "passive"))
    )
  )
)
